# STM32.net
KiCad netlist of a schematic drawn in Altium Designer
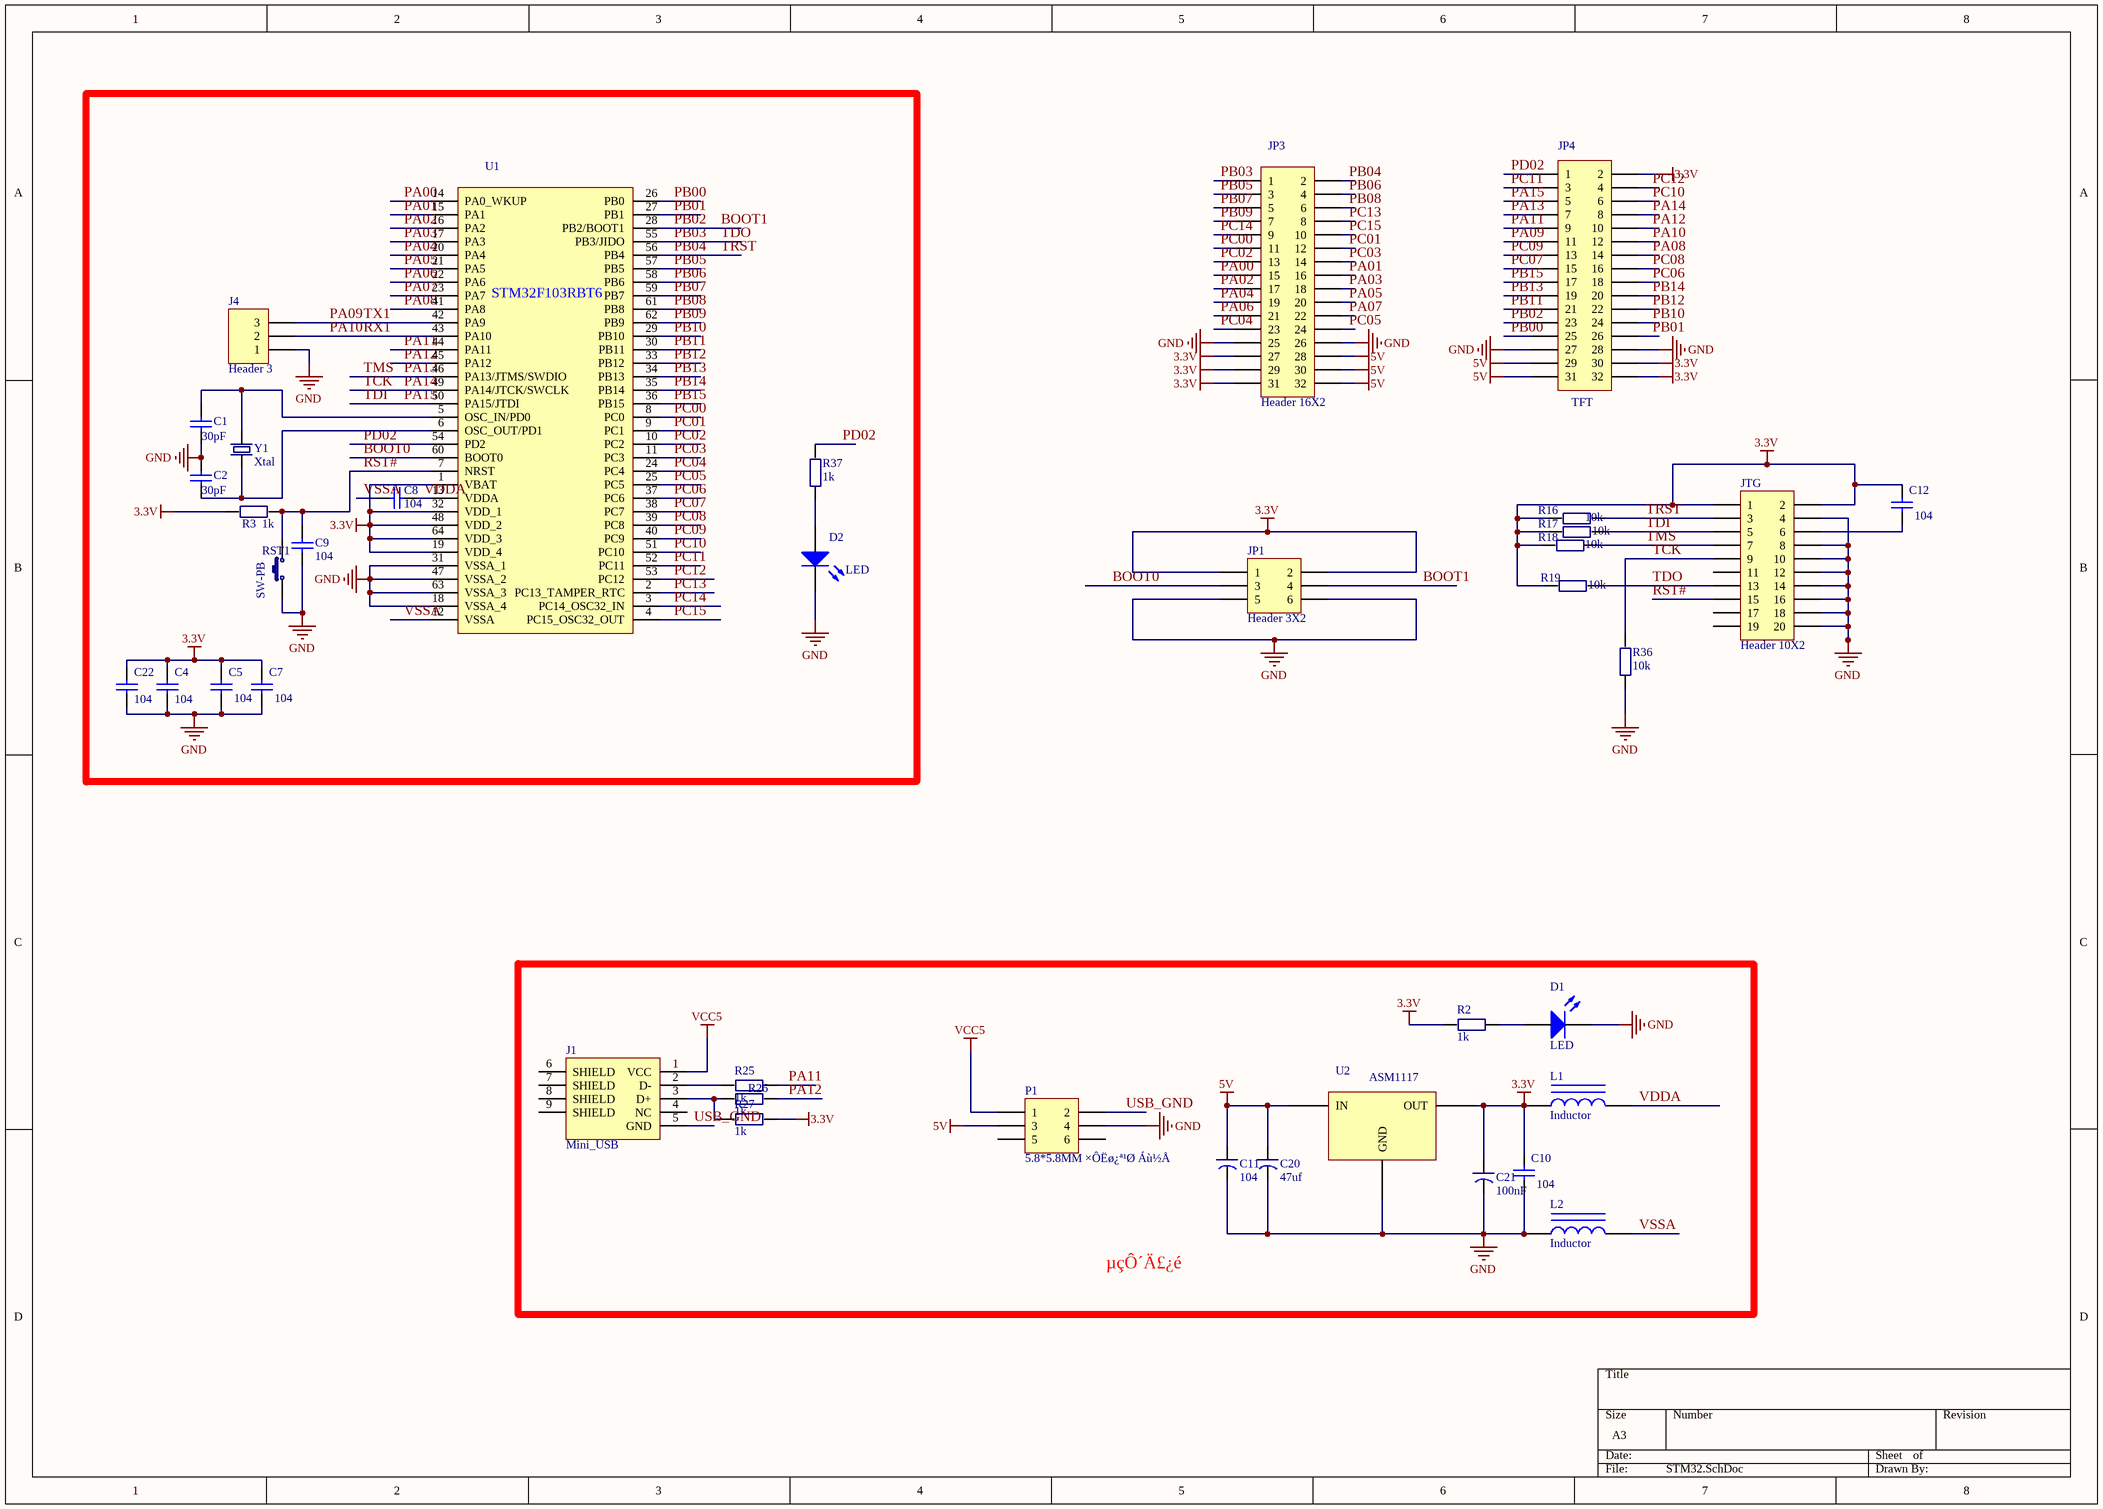
[diagram p0: STM32.SchDoc]

(export (version "E")
  (design (tool "Eeschema 10.0.6"))
  (components
    (comp (ref "C1")
      (value "30pF")
      (footprint "C0805")
      (description "Capacitor")
      (fields (field (name "Comment") "Cap") (field (name "PUBLISHER") "Altium Limited"))
      (libsource (lib "M051电子称") (part "Cap"))
    )
    (comp (ref "C2")
      (value "30pF")
      (footprint "C0805")
      (description "Capacitor")
      (fields (field (name "Comment") "Cap") (field (name "PUBLISHER") "Altium Limited"))
      (libsource (lib "M051电子称") (part "Cap"))
    )
    (comp (ref "C4")
      (value "104")
      (footprint "C0805")
      (description "Capacitor")
      (fields (field (name "Comment") "Cap") (field (name "PUBLISHER") "Altium Limited"))
      (libsource (lib "M051电子称") (part "Cap"))
    )
    (comp (ref "C5")
      (value "104")
      (footprint "C0805")
      (description "Capacitor")
      (fields (field (name "Comment") "Cap") (field (name "PUBLISHER") "Altium Limited"))
      (libsource (lib "M051电子称") (part "Cap"))
    )
    (comp (ref "C7")
      (value "104")
      (footprint "C0805")
      (description "Capacitor")
      (fields (field (name "Comment") "Cap") (field (name "PUBLISHER") "Altium Limited"))
      (libsource (lib "M051电子称") (part "Cap"))
    )
    (comp (ref "C8")
      (value "104")
      (footprint "C0805")
      (description "Capacitor")
      (fields (field (name "Comment") "Cap") (field (name "PUBLISHER") "Altium Limited"))
      (libsource (lib "M051电子称") (part "Cap"))
    )
    (comp (ref "C9")
      (value "104")
      (footprint "C0805")
      (description "Capacitor")
      (fields (field (name "Comment") "Cap") (field (name "PUBLISHER") "Altium Limited"))
      (libsource (lib "M051电子称") (part "Cap"))
    )
    (comp (ref "C10")
      (value "104")
      (footprint "C0805")
      (description "Capacitor")
      (fields (field (name "Comment") "Cap") (field (name "PUBLISHER") "Altium Limited"))
      (libsource (lib "M051电子称") (part "Cap"))
    )
    (comp (ref "C11")
      (value "104")
      (footprint "C0805")
      (fields (field (name "Comment") "Capacitor"))
      (libsource (lib "My Devices") (part "Capacitor"))
    )
    (comp (ref "C12")
      (value "104")
      (footprint "C0805")
      (description "Capacitor")
      (fields (field (name "Comment") "Cap") (field (name "PUBLISHER") "Altium Limited"))
      (libsource (lib "M051电子称") (part "Cap"))
    )
    (comp (ref "C20")
      (value "47uf")
      (footprint "47uF_25V")
      (fields (field (name "Comment") "Capacitor"))
      (libsource (lib "My Devices") (part "Capacitor"))
    )
    (comp (ref "C21")
      (value "100nF")
      (footprint "47uF_25V")
      (fields (field (name "Comment") "Capacitor"))
      (libsource (lib "My Devices") (part "Capacitor"))
    )
    (comp (ref "C22")
      (value "104")
      (footprint "C0805")
      (description "Capacitor")
      (fields (field (name "Comment") "Cap") (field (name "PUBLISHER") "Altium Limited"))
      (libsource (lib "M051电子称") (part "Cap"))
    )
    (comp (ref "D1") (value "LED") (footprint "0805D") (libsource (lib "My Devices") (part "LED")))
    (comp (ref "D2") (value "LED") (footprint "0805D") (libsource (lib "My Devices") (part "LED")))
    (comp (ref "J1")
      (value "Mini_USB")
      (footprint "Mini_USB")
      (libsource (lib "My Devices") (part "Mini_USB"))
    )
    (comp (ref "J4")
      (value "Header 3")
      (footprint "HDR1X3")
      (description "Header, 3-Pin")
      (fields (field (name "PUBLISHER") "Altium Limited"))
      (libsource (lib "Header Devices") (part "Header 3"))
    )
    (comp (ref "JP1")
      (value "Header 3X2")
      (footprint "HDR2X3")
      (description "Header, 3-Pin, Dual row")
      (fields (field (name "PUBLISHER") "Altium Limited"))
      (libsource (lib "Header Devices") (part "Header 3X2"))
    )
    (comp (ref "JP3")
      (value "Header 16X2")
      (footprint "HDR2X16")
      (description "Header, 16-Pin, Dual row")
      (fields (field (name "PUBLISHER") "Altium Limited"))
      (libsource (lib "Header Devices") (part "Header 16X2"))
    )
    (comp (ref "JP4")
      (value "TFT")
      (footprint "HDR2X16")
      (description "Header, 16-Pin, Dual row")
      (fields (field (name "PUBLISHER") "Altium Limited"))
      (libsource (lib "Header Devices") (part "Header 16X2"))
    )
    (comp (ref "JTG")
      (value "Header 10X2")
      (footprint "HDR2X10")
      (description "Header, 10-Pin, Dual row")
      (fields (field (name "PUBLISHER") "Altium Limited"))
      (libsource (lib "Header Devices") (part "Header 10X2"))
    )
    (comp (ref "L1") (value "Inductor") (footprint "C0805") (libsource (lib "My Devices") (part "Inductor")))
    (comp (ref "L2") (value "Inductor") (footprint "C0805") (libsource (lib "My Devices") (part "Inductor")))
    (comp (ref "P1")
      (value "5.8*5.8MM 自锁开关 六脚")
      (footprint "5.8*5.8MM 自锁开关 六脚")
      (libsource (lib "自制库-程文") (part "5.8*5.8MM 自锁开关 六脚"))
    )
    (comp (ref "R2")
      (value "1k")
      (footprint "R0805")
      (fields (field (name "Comment") "Resistor"))
      (libsource (lib "My Devices") (part "Resistor"))
    )
    (comp (ref "R3")
      (value "1k")
      (footprint "R0805")
      (fields (field (name "Comment") "Resistor"))
      (libsource (lib "My Devices") (part "Resistor"))
    )
    (comp (ref "R16")
      (value "10k")
      (footprint "R0805")
      (fields (field (name "Comment") "Resistor"))
      (libsource (lib "My Devices") (part "Resistor"))
    )
    (comp (ref "R17")
      (value "10k")
      (footprint "R0805")
      (fields (field (name "Comment") "Resistor"))
      (libsource (lib "My Devices") (part "Resistor"))
    )
    (comp (ref "R18")
      (value "10k")
      (footprint "R0805")
      (fields (field (name "Comment") "Resistor"))
      (libsource (lib "My Devices") (part "Resistor"))
    )
    (comp (ref "R19")
      (value "10k")
      (footprint "R0805")
      (fields (field (name "Comment") "Resistor"))
      (libsource (lib "My Devices") (part "Resistor"))
    )
    (comp (ref "R25")
      (value "1k")
      (footprint "R0805")
      (fields (field (name "Comment") "Resistor"))
      (libsource (lib "My Devices") (part "Resistor"))
    )
    (comp (ref "R26")
      (value "1k")
      (footprint "R0805")
      (fields (field (name "Comment") "Resistor"))
      (libsource (lib "My Devices") (part "Resistor"))
    )
    (comp (ref "R27")
      (value "1k")
      (footprint "R0805")
      (fields (field (name "Comment") "Resistor"))
      (libsource (lib "My Devices") (part "Resistor"))
    )
    (comp (ref "R36")
      (value "10k")
      (footprint "R0805")
      (fields (field (name "Comment") "Resistor"))
      (libsource (lib "My Devices") (part "Resistor"))
    )
    (comp (ref "R37")
      (value "1k")
      (footprint "R0805")
      (fields (field (name "Comment") "Resistor"))
      (libsource (lib "My Devices") (part "Resistor"))
    )
    (comp (ref "RST1") (value "SW-PB") (footprint "TD-19XA") (libsource (lib "My Devices") (part "Switch")))
    (comp (ref "U1")
      (value "STM32F103RBT6")
      (footprint "LQFP-64N")
      (libsource (lib "My Devices") (part "STM32F103RBT6"))
    )
    (comp (ref "U2") (value "ASM1117") (footprint "SOT-223") (libsource (lib "电源类集成库") (part "ASM1117")))
    (comp (ref "Y1") (value "Xtal") (footprint "CRYSTAL") (libsource (lib "My Devices") (part "Xtal")))
  )
  (nets
    (net (code "1") (name "/BOOT0") (class "Default")
      (node (ref "JP1") (pin "3") (pinfunction "3_3") (pintype "passive"))
      (node (ref "U1") (pin "60") (pinfunction "BOOT0_60") (pintype "passive"))
    )
    (net (code "2") (name "/BOOT1") (class "Default")
      (node (ref "JP1") (pin "4") (pinfunction "4_4") (pintype "passive"))
      (node (ref "JP4") (pin "23") (pinfunction "23_23") (pintype "passive"))
      (node (ref "U1") (pin "28") (pinfunction "PB2/BOOT1_28") (pintype "passive"))
    )
    (net (code "3") (name "/PA00") (class "Default")
      (node (ref "JP3") (pin "15") (pinfunction "15_15") (pintype "passive"))
      (node (ref "U1") (pin "14") (pinfunction "PA0_WKUP_14") (pintype "passive"))
    )
    (net (code "4") (name "/PA01") (class "Default")
      (node (ref "JP3") (pin "16") (pinfunction "16_16") (pintype "passive"))
      (node (ref "U1") (pin "15") (pinfunction "PA1_15") (pintype "passive"))
    )
    (net (code "5") (name "/PA02") (class "Default")
      (node (ref "JP3") (pin "17") (pinfunction "17_17") (pintype "passive"))
      (node (ref "U1") (pin "16") (pinfunction "PA2_16") (pintype "passive"))
    )
    (net (code "6") (name "/PA03") (class "Default")
      (node (ref "JP3") (pin "18") (pinfunction "18_18") (pintype "passive"))
      (node (ref "U1") (pin "17") (pinfunction "PA3_17") (pintype "passive"))
    )
    (net (code "7") (name "/PA04") (class "Default")
      (node (ref "JP3") (pin "19") (pinfunction "19_19") (pintype "passive"))
      (node (ref "U1") (pin "20") (pinfunction "PA4_20") (pintype "passive"))
    )
    (net (code "8") (name "/PA05") (class "Default")
      (node (ref "JP3") (pin "20") (pinfunction "20_20") (pintype "passive"))
      (node (ref "U1") (pin "21") (pinfunction "PA5_21") (pintype "passive"))
    )
    (net (code "9") (name "/PA06") (class "Default")
      (node (ref "JP3") (pin "21") (pinfunction "21_21") (pintype "passive"))
      (node (ref "U1") (pin "22") (pinfunction "PA6_22") (pintype "passive"))
    )
    (net (code "10") (name "/PA07") (class "Default")
      (node (ref "JP3") (pin "22") (pinfunction "22_22") (pintype "passive"))
      (node (ref "U1") (pin "23") (pinfunction "PA7_23") (pintype "passive"))
    )
    (net (code "11") (name "/PA08") (class "Default")
      (node (ref "JP4") (pin "14") (pinfunction "14_14") (pintype "passive"))
      (node (ref "U1") (pin "41") (pinfunction "PA8_41") (pintype "passive"))
    )
    (net (code "12") (name "/PA09") (class "Default")
      (node (ref "J4") (pin "3") (pinfunction "3_3") (pintype "passive"))
      (node (ref "JP4") (pin "11") (pinfunction "11_11") (pintype "passive"))
      (node (ref "U1") (pin "42") (pinfunction "PA9_42") (pintype "passive"))
    )
    (net (code "13") (name "/PA10") (class "Default")
      (node (ref "J4") (pin "2") (pinfunction "2_2") (pintype "passive"))
      (node (ref "JP4") (pin "12") (pinfunction "12_12") (pintype "passive"))
      (node (ref "U1") (pin "43") (pinfunction "PA10_43") (pintype "passive"))
    )
    (net (code "14") (name "/PA11") (class "Default")
      (node (ref "JP4") (pin "9") (pinfunction "9_9") (pintype "passive"))
      (node (ref "R25") (pin "1") (pintype "passive"))
      (node (ref "U1") (pin "44") (pinfunction "PA11_44") (pintype "passive"))
    )
    (net (code "15") (name "/PA12") (class "Default")
      (node (ref "JP4") (pin "10") (pinfunction "10_10") (pintype "passive"))
      (node (ref "R26") (pin "1") (pintype "passive"))
      (node (ref "U1") (pin "45") (pinfunction "PA12_45") (pintype "passive"))
    )
    (net (code "16") (name "/PA13") (class "Default")
      (node (ref "JP4") (pin "7") (pinfunction "7_7") (pintype "passive"))
      (node (ref "JTG") (pin "7") (pinfunction "7_7") (pintype "passive"))
      (node (ref "R18") (pin "1") (pintype "passive"))
      (node (ref "U1") (pin "46") (pinfunction "PA13/JTMS/SWDIO_46") (pintype "passive"))
    )
    (net (code "17") (name "/PA14") (class "Default")
      (node (ref "JP4") (pin "8") (pinfunction "8_8") (pintype "passive"))
      (node (ref "JTG") (pin "9") (pinfunction "9_9") (pintype "passive"))
      (node (ref "R36") (pin "1") (pintype "passive"))
      (node (ref "U1") (pin "49") (pinfunction "PA14/JTCK/SWCLK_49") (pintype "passive"))
    )
    (net (code "18") (name "/PA15") (class "Default")
      (node (ref "JP4") (pin "5") (pinfunction "5_5") (pintype "passive"))
      (node (ref "JTG") (pin "5") (pinfunction "5_5") (pintype "passive"))
      (node (ref "R17") (pin "1") (pintype "passive"))
      (node (ref "U1") (pin "50") (pinfunction "PA15/JTDI_50") (pintype "passive"))
    )
    (net (code "19") (name "/PB00") (class "Default")
      (node (ref "JP4") (pin "25") (pinfunction "25_25") (pintype "passive"))
      (node (ref "U1") (pin "26") (pinfunction "PB0_26") (pintype "passive"))
    )
    (net (code "20") (name "/PB01") (class "Default")
      (node (ref "JP4") (pin "26") (pinfunction "26_26") (pintype "passive"))
      (node (ref "U1") (pin "27") (pinfunction "PB1_27") (pintype "passive"))
    )
    (net (code "21") (name "/PB03") (class "Default")
      (node (ref "JP3") (pin "1") (pinfunction "1_1") (pintype "passive"))
      (node (ref "JTG") (pin "13") (pinfunction "13_13") (pintype "passive"))
      (node (ref "R19") (pin "1") (pintype "passive"))
      (node (ref "U1") (pin "55") (pinfunction "PB3/JIDO_55") (pintype "passive"))
    )
    (net (code "22") (name "/PB04") (class "Default")
      (node (ref "JP3") (pin "2") (pinfunction "2_2") (pintype "passive"))
      (node (ref "JTG") (pin "3") (pinfunction "3_3") (pintype "passive"))
      (node (ref "R16") (pin "1") (pintype "passive"))
      (node (ref "U1") (pin "56") (pinfunction "PB4_56") (pintype "passive"))
    )
    (net (code "23") (name "/PB05") (class "Default")
      (node (ref "JP3") (pin "3") (pinfunction "3_3") (pintype "passive"))
      (node (ref "U1") (pin "57") (pinfunction "PB5_57") (pintype "passive"))
    )
    (net (code "24") (name "/PB06") (class "Default")
      (node (ref "JP3") (pin "4") (pinfunction "4_4") (pintype "passive"))
      (node (ref "U1") (pin "58") (pinfunction "PB6_58") (pintype "passive"))
    )
    (net (code "25") (name "/PB07") (class "Default")
      (node (ref "JP3") (pin "5") (pinfunction "5_5") (pintype "passive"))
      (node (ref "U1") (pin "59") (pinfunction "PB7_59") (pintype "passive"))
    )
    (net (code "26") (name "/PB08") (class "Default")
      (node (ref "JP3") (pin "6") (pinfunction "6_6") (pintype "passive"))
      (node (ref "U1") (pin "61") (pinfunction "PB8_61") (pintype "passive"))
    )
    (net (code "27") (name "/PB09") (class "Default")
      (node (ref "JP3") (pin "7") (pinfunction "7_7") (pintype "passive"))
      (node (ref "U1") (pin "62") (pinfunction "PB9_62") (pintype "passive"))
    )
    (net (code "28") (name "/PB10") (class "Default")
      (node (ref "JP4") (pin "24") (pinfunction "24_24") (pintype "passive"))
      (node (ref "U1") (pin "29") (pinfunction "PB10_29") (pintype "passive"))
    )
    (net (code "29") (name "/PB11") (class "Default")
      (node (ref "JP4") (pin "21") (pinfunction "21_21") (pintype "passive"))
      (node (ref "U1") (pin "30") (pinfunction "PB11_30") (pintype "passive"))
    )
    (net (code "30") (name "/PB12") (class "Default")
      (node (ref "JP4") (pin "22") (pinfunction "22_22") (pintype "passive"))
      (node (ref "U1") (pin "33") (pinfunction "PB12_33") (pintype "passive"))
    )
    (net (code "31") (name "/PB13") (class "Default")
      (node (ref "JP4") (pin "19") (pinfunction "19_19") (pintype "passive"))
      (node (ref "U1") (pin "34") (pinfunction "PB13_34") (pintype "passive"))
    )
    (net (code "32") (name "/PB14") (class "Default")
      (node (ref "JP4") (pin "20") (pinfunction "20_20") (pintype "passive"))
      (node (ref "U1") (pin "35") (pinfunction "PB14_35") (pintype "passive"))
    )
    (net (code "33") (name "/PB15") (class "Default")
      (node (ref "JP4") (pin "17") (pinfunction "17_17") (pintype "passive"))
      (node (ref "U1") (pin "36") (pinfunction "PB15_36") (pintype "passive"))
    )
    (net (code "34") (name "/PC00") (class "Default")
      (node (ref "JP3") (pin "11") (pinfunction "11_11") (pintype "passive"))
      (node (ref "U1") (pin "8") (pinfunction "PC0_8") (pintype "passive"))
    )
    (net (code "35") (name "/PC01") (class "Default")
      (node (ref "JP3") (pin "12") (pinfunction "12_12") (pintype "passive"))
      (node (ref "U1") (pin "9") (pinfunction "PC1_9") (pintype "passive"))
    )
    (net (code "36") (name "/PC02") (class "Default")
      (node (ref "JP3") (pin "13") (pinfunction "13_13") (pintype "passive"))
      (node (ref "U1") (pin "10") (pinfunction "PC2_10") (pintype "passive"))
    )
    (net (code "37") (name "/PC03") (class "Default")
      (node (ref "JP3") (pin "14") (pinfunction "14_14") (pintype "passive"))
      (node (ref "U1") (pin "11") (pinfunction "PC3_11") (pintype "passive"))
    )
    (net (code "38") (name "/PC04") (class "Default")
      (node (ref "JP3") (pin "23") (pinfunction "23_23") (pintype "passive"))
      (node (ref "U1") (pin "24") (pinfunction "PC4_24") (pintype "passive"))
    )
    (net (code "39") (name "/PC05") (class "Default")
      (node (ref "JP3") (pin "24") (pinfunction "24_24") (pintype "passive"))
      (node (ref "U1") (pin "25") (pinfunction "PC5_25") (pintype "passive"))
    )
    (net (code "40") (name "/PC06") (class "Default")
      (node (ref "JP4") (pin "18") (pinfunction "18_18") (pintype "passive"))
      (node (ref "U1") (pin "37") (pinfunction "PC6_37") (pintype "passive"))
    )
    (net (code "41") (name "/PC07") (class "Default")
      (node (ref "JP4") (pin "15") (pinfunction "15_15") (pintype "passive"))
      (node (ref "U1") (pin "38") (pinfunction "PC7_38") (pintype "passive"))
    )
    (net (code "42") (name "/PC08") (class "Default")
      (node (ref "JP4") (pin "16") (pinfunction "16_16") (pintype "passive"))
      (node (ref "U1") (pin "39") (pinfunction "PC8_39") (pintype "passive"))
    )
    (net (code "43") (name "/PC09") (class "Default")
      (node (ref "JP4") (pin "13") (pinfunction "13_13") (pintype "passive"))
      (node (ref "U1") (pin "40") (pinfunction "PC9_40") (pintype "passive"))
    )
    (net (code "44") (name "/PC10") (class "Default")
      (node (ref "JP4") (pin "6") (pinfunction "6_6") (pintype "passive"))
      (node (ref "U1") (pin "51") (pinfunction "PC10_51") (pintype "passive"))
    )
    (net (code "45") (name "/PC11") (class "Default")
      (node (ref "JP4") (pin "3") (pinfunction "3_3") (pintype "passive"))
      (node (ref "U1") (pin "52") (pinfunction "PC11_52") (pintype "passive"))
    )
    (net (code "46") (name "/PC12") (class "Default")
      (node (ref "JP4") (pin "4") (pinfunction "4_4") (pintype "passive"))
      (node (ref "U1") (pin "53") (pinfunction "PC12_53") (pintype "passive"))
    )
    (net (code "47") (name "/PC13") (class "Default")
      (node (ref "JP3") (pin "8") (pinfunction "8_8") (pintype "passive"))
      (node (ref "U1") (pin "2") (pinfunction "PC13_TAMPER_RTC_2") (pintype "passive"))
    )
    (net (code "48") (name "/PC14") (class "Default")
      (node (ref "JP3") (pin "9") (pinfunction "9_9") (pintype "passive"))
      (node (ref "U1") (pin "3") (pinfunction "PC14_OSC32_IN_3") (pintype "passive"))
    )
    (net (code "49") (name "/PC15") (class "Default")
      (node (ref "JP3") (pin "10") (pinfunction "10_10") (pintype "passive"))
      (node (ref "U1") (pin "4") (pinfunction "PC15_OSC32_OUT_4") (pintype "passive"))
    )
    (net (code "50") (name "/PD02") (class "Default")
      (node (ref "JP4") (pin "1") (pinfunction "1_1") (pintype "passive"))
      (node (ref "R37") (pin "2") (pintype "passive"))
      (node (ref "U1") (pin "54") (pinfunction "PD2_54") (pintype "passive"))
    )
    (net (code "51") (name "/RST#") (class "Default")
      (node (ref "C9") (pin "1") (pinfunction "1_1") (pintype "passive"))
      (node (ref "JTG") (pin "15") (pinfunction "15_15") (pintype "passive"))
      (node (ref "R3") (pin "2") (pintype "passive"))
      (node (ref "RST1") (pin "2") (pinfunction "1_2") (pintype "passive"))
      (node (ref "U1") (pin "7") (pinfunction "NRST_7") (pintype "passive"))
    )
    (net (code "52") (name "/USB_GND") (class "Default")
      (node (ref "J1") (pin "5") (pinfunction "GND_5") (pintype "passive"))
      (node (ref "P1") (pin "2") (pinfunction "2_2") (pintype "passive"))
    )
    (net (code "53") (name "/VDDA") (class "Default")
      (node (ref "C8") (pin "1") (pinfunction "1_1") (pintype "passive"))
      (node (ref "L1") (pin "2") (pinfunction "2_2") (pintype "passive"))
      (node (ref "U1") (pin "13") (pinfunction "VDDA_13") (pintype "passive"))
    )
    (net (code "54") (name "/VSSA") (class "Default")
      (node (ref "C8") (pin "2") (pinfunction "2_2") (pintype "passive"))
      (node (ref "L2") (pin "2") (pinfunction "2_2") (pintype "passive"))
      (node (ref "U1") (pin "12") (pinfunction "VSSA_12") (pintype "passive"))
    )
    (net (code "55") (name "3.3V") (class "Default")
      (node (ref "C10") (pin "1") (pinfunction "1_1") (pintype "passive"))
      (node (ref "C12") (pin "1") (pinfunction "1_1") (pintype "passive"))
      (node (ref "C21") (pin "1") (pinfunction "0_1") (pintype "passive"))
      (node (ref "C22") (pin "1") (pinfunction "1_1") (pintype "passive"))
      (node (ref "C4") (pin "1") (pinfunction "1_1") (pintype "passive"))
      (node (ref "C5") (pin "1") (pinfunction "1_1") (pintype "passive"))
      (node (ref "C7") (pin "1") (pinfunction "1_1") (pintype "passive"))
      (node (ref "JP1") (pin "1") (pinfunction "1_1") (pintype "passive"))
      (node (ref "JP1") (pin "2") (pinfunction "2_2") (pintype "passive"))
      (node (ref "JP3") (pin "27") (pinfunction "27_27") (pintype "passive"))
      (node (ref "JP3") (pin "29") (pinfunction "29_29") (pintype "passive"))
      (node (ref "JP3") (pin "31") (pinfunction "31_31") (pintype "passive"))
      (node (ref "JP4") (pin "2") (pinfunction "2_2") (pintype "passive"))
      (node (ref "JP4") (pin "30") (pinfunction "30_30") (pintype "passive"))
      (node (ref "JP4") (pin "32") (pinfunction "32_32") (pintype "passive"))
      (node (ref "JTG") (pin "1") (pinfunction "1_1") (pintype "passive"))
      (node (ref "JTG") (pin "2") (pinfunction "2_2") (pintype "passive"))
      (node (ref "L1") (pin "1") (pinfunction "1_1") (pintype "passive"))
      (node (ref "R16") (pin "2") (pintype "passive"))
      (node (ref "R17") (pin "2") (pintype "passive"))
      (node (ref "R18") (pin "2") (pintype "passive"))
      (node (ref "R19") (pin "2") (pintype "passive"))
      (node (ref "R2") (pin "2") (pintype "passive"))
      (node (ref "R27") (pin "1") (pintype "passive"))
      (node (ref "R3") (pin "1") (pintype "passive"))
      (node (ref "U1") (pin "1") (pinfunction "VBAT_1") (pintype "passive"))
      (node (ref "U1") (pin "19") (pinfunction "VDD_4_19") (pintype "passive"))
      (node (ref "U1") (pin "32") (pinfunction "VDD_1_32") (pintype "passive"))
      (node (ref "U1") (pin "48") (pinfunction "VDD_2_48") (pintype "passive"))
      (node (ref "U1") (pin "64") (pinfunction "VDD_3_64") (pintype "passive"))
      (node (ref "U2") (pin "2") (pinfunction "OUT_2") (pintype "passive"))
    )
    (net (code "56") (name "5V") (class "Default")
      (node (ref "C11") (pin "1") (pinfunction "0_1") (pintype "passive"))
      (node (ref "C20") (pin "1") (pinfunction "0_1") (pintype "passive"))
      (node (ref "JP3") (pin "28") (pinfunction "28_28") (pintype "passive"))
      (node (ref "JP3") (pin "30") (pinfunction "30_30") (pintype "passive"))
      (node (ref "JP3") (pin "32") (pinfunction "32_32") (pintype "passive"))
      (node (ref "JP4") (pin "29") (pinfunction "29_29") (pintype "passive"))
      (node (ref "JP4") (pin "31") (pinfunction "31_31") (pintype "passive"))
      (node (ref "P1") (pin "3") (pinfunction "3_3") (pintype "passive"))
      (node (ref "U2") (pin "3") (pinfunction "IN_3") (pintype "passive"))
    )
    (net (code "57") (name "GND") (class "Default")
      (node (ref "C1") (pin "1") (pinfunction "1_1") (pintype "passive"))
      (node (ref "C10") (pin "2") (pinfunction "2_2") (pintype "passive"))
      (node (ref "C11") (pin "2") (pinfunction "1_2") (pintype "passive"))
      (node (ref "C2") (pin "2") (pinfunction "2_2") (pintype "passive"))
      (node (ref "C20") (pin "2") (pinfunction "1_2") (pintype "passive"))
      (node (ref "C21") (pin "2") (pinfunction "1_2") (pintype "passive"))
      (node (ref "C22") (pin "2") (pinfunction "2_2") (pintype "passive"))
      (node (ref "C4") (pin "2") (pinfunction "2_2") (pintype "passive"))
      (node (ref "C5") (pin "2") (pinfunction "2_2") (pintype "passive"))
      (node (ref "C7") (pin "2") (pinfunction "2_2") (pintype "passive"))
      (node (ref "C9") (pin "2") (pinfunction "2_2") (pintype "passive"))
      (node (ref "D1") (pin "2") (pinfunction "K_2") (pintype "passive"))
      (node (ref "D2") (pin "2") (pinfunction "K_2") (pintype "passive"))
      (node (ref "J4") (pin "1") (pinfunction "1_1") (pintype "passive"))
      (node (ref "JP1") (pin "5") (pinfunction "5_5") (pintype "passive"))
      (node (ref "JP1") (pin "6") (pinfunction "6_6") (pintype "passive"))
      (node (ref "JP3") (pin "25") (pinfunction "25_25") (pintype "passive"))
      (node (ref "JP3") (pin "26") (pinfunction "26_26") (pintype "passive"))
      (node (ref "JP4") (pin "27") (pinfunction "27_27") (pintype "passive"))
      (node (ref "JP4") (pin "28") (pinfunction "28_28") (pintype "passive"))
      (node (ref "JTG") (pin "10") (pinfunction "10_10") (pintype "passive"))
      (node (ref "JTG") (pin "12") (pinfunction "12_12") (pintype "passive"))
      (node (ref "JTG") (pin "14") (pinfunction "14_14") (pintype "passive"))
      (node (ref "JTG") (pin "16") (pinfunction "16_16") (pintype "passive"))
      (node (ref "JTG") (pin "18") (pinfunction "18_18") (pintype "passive"))
      (node (ref "JTG") (pin "20") (pinfunction "20_20") (pintype "passive"))
      (node (ref "JTG") (pin "4") (pinfunction "4_4") (pintype "passive"))
      (node (ref "JTG") (pin "8") (pinfunction "8_8") (pintype "passive"))
      (node (ref "L2") (pin "1") (pinfunction "1_1") (pintype "passive"))
      (node (ref "P1") (pin "4") (pinfunction "4_4") (pintype "passive"))
      (node (ref "R36") (pin "2") (pintype "passive"))
      (node (ref "RST1") (pin "1") (pinfunction "0_1") (pintype "passive"))
      (node (ref "U1") (pin "18") (pinfunction "VSSA_4_18") (pintype "passive"))
      (node (ref "U1") (pin "31") (pinfunction "VSSA_1_31") (pintype "passive"))
      (node (ref "U1") (pin "47") (pinfunction "VSSA_2_47") (pintype "passive"))
      (node (ref "U1") (pin "63") (pinfunction "VSSA_3_63") (pintype "passive"))
      (node (ref "U2") (pin "1") (pinfunction "GND_1") (pintype "passive"))
    )
    (net (code "58") (name "Net-(C12-Pad2)") (class "Default")
      (node (ref "C12") (pin "2") (pinfunction "2_2") (pintype "passive"))
      (node (ref "JTG") (pin "6") (pinfunction "6_6") (pintype "passive"))
    )
    (net (code "59") (name "Net-(D1-A)") (class "Default")
      (node (ref "D1") (pin "1") (pinfunction "A_1") (pintype "passive"))
      (node (ref "R2") (pin "1") (pintype "passive"))
    )
    (net (code "60") (name "Net-(D2-A)") (class "Default")
      (node (ref "D2") (pin "1") (pinfunction "A_1") (pintype "passive"))
      (node (ref "R37") (pin "1") (pintype "passive"))
    )
    (net (code "61") (name "Net-(J1-D+)") (class "Default")
      (node (ref "J1") (pin "3") (pinfunction "D+_3") (pintype "passive"))
      (node (ref "R26") (pin "2") (pintype "passive"))
      (node (ref "R27") (pin "2") (pintype "passive"))
    )
    (net (code "62") (name "Net-(J1-D-)") (class "Default")
      (node (ref "J1") (pin "2") (pinfunction "D-_2") (pintype "passive"))
      (node (ref "R25") (pin "2") (pintype "passive"))
    )
    (net (code "63") (name "Net-(U1-OSC_IN{slash}PD0)") (class "Default")
      (node (ref "C1") (pin "2") (pinfunction "2_2") (pintype "passive"))
      (node (ref "U1") (pin "5") (pinfunction "OSC_IN/PD0_5") (pintype "passive"))
      (node (ref "Y1") (pin "2") (pinfunction "1_2") (pintype "passive"))
    )
    (net (code "64") (name "Net-(U1-OSC_OUT{slash}PD1)") (class "Default")
      (node (ref "C2") (pin "1") (pinfunction "1_1") (pintype "passive"))
      (node (ref "U1") (pin "6") (pinfunction "OSC_OUT/PD1_6") (pintype "passive"))
      (node (ref "Y1") (pin "1") (pinfunction "0_1") (pintype "passive"))
    )
    (net (code "65") (name "VCC5") (class "Default")
      (node (ref "J1") (pin "1") (pinfunction "VCC_1") (pintype "passive"))
      (node (ref "P1") (pin "1") (pinfunction "1_1") (pintype "passive"))
    )
    (net (code "66") (name "unconnected-(J1-NC-Pad4)") (class "Default")
      (node (ref "J1") (pin "4") (pinfunction "NC_4") (pintype "passive"))
    )
    (net (code "67") (name "unconnected-(J1-SHIELD-Pad6)") (class "Default")
      (node (ref "J1") (pin "6") (pinfunction "SHIELD_6") (pintype "passive"))
    )
    (net (code "68") (name "unconnected-(J1-SHIELD-Pad7)") (class "Default")
      (node (ref "J1") (pin "7") (pinfunction "SHIELD_7") (pintype "passive"))
    )
    (net (code "69") (name "unconnected-(J1-SHIELD-Pad8)") (class "Default")
      (node (ref "J1") (pin "8") (pinfunction "SHIELD_8") (pintype "passive"))
    )
    (net (code "70") (name "unconnected-(J1-SHIELD-Pad9)") (class "Default")
      (node (ref "J1") (pin "9") (pinfunction "SHIELD_9") (pintype "passive"))
    )
    (net (code "71") (name "unconnected-(JTG-Pad11)") (class "Default")
      (node (ref "JTG") (pin "11") (pinfunction "11_11") (pintype "passive"))
    )
    (net (code "72") (name "unconnected-(JTG-Pad17)") (class "Default")
      (node (ref "JTG") (pin "17") (pinfunction "17_17") (pintype "passive"))
    )
    (net (code "73") (name "unconnected-(JTG-Pad19)") (class "Default")
      (node (ref "JTG") (pin "19") (pinfunction "19_19") (pintype "passive"))
    )
    (net (code "74") (name "unconnected-(P1-Pad5)") (class "Default")
      (node (ref "P1") (pin "5") (pinfunction "5_5") (pintype "passive"))
    )
    (net (code "75") (name "unconnected-(P1-Pad6)") (class "Default")
      (node (ref "P1") (pin "6") (pinfunction "6_6") (pintype "passive"))
    )
  )
)
